# SCH_CyGarageM2.net
KiCad netlist of a schematic drawn in EasyEDA
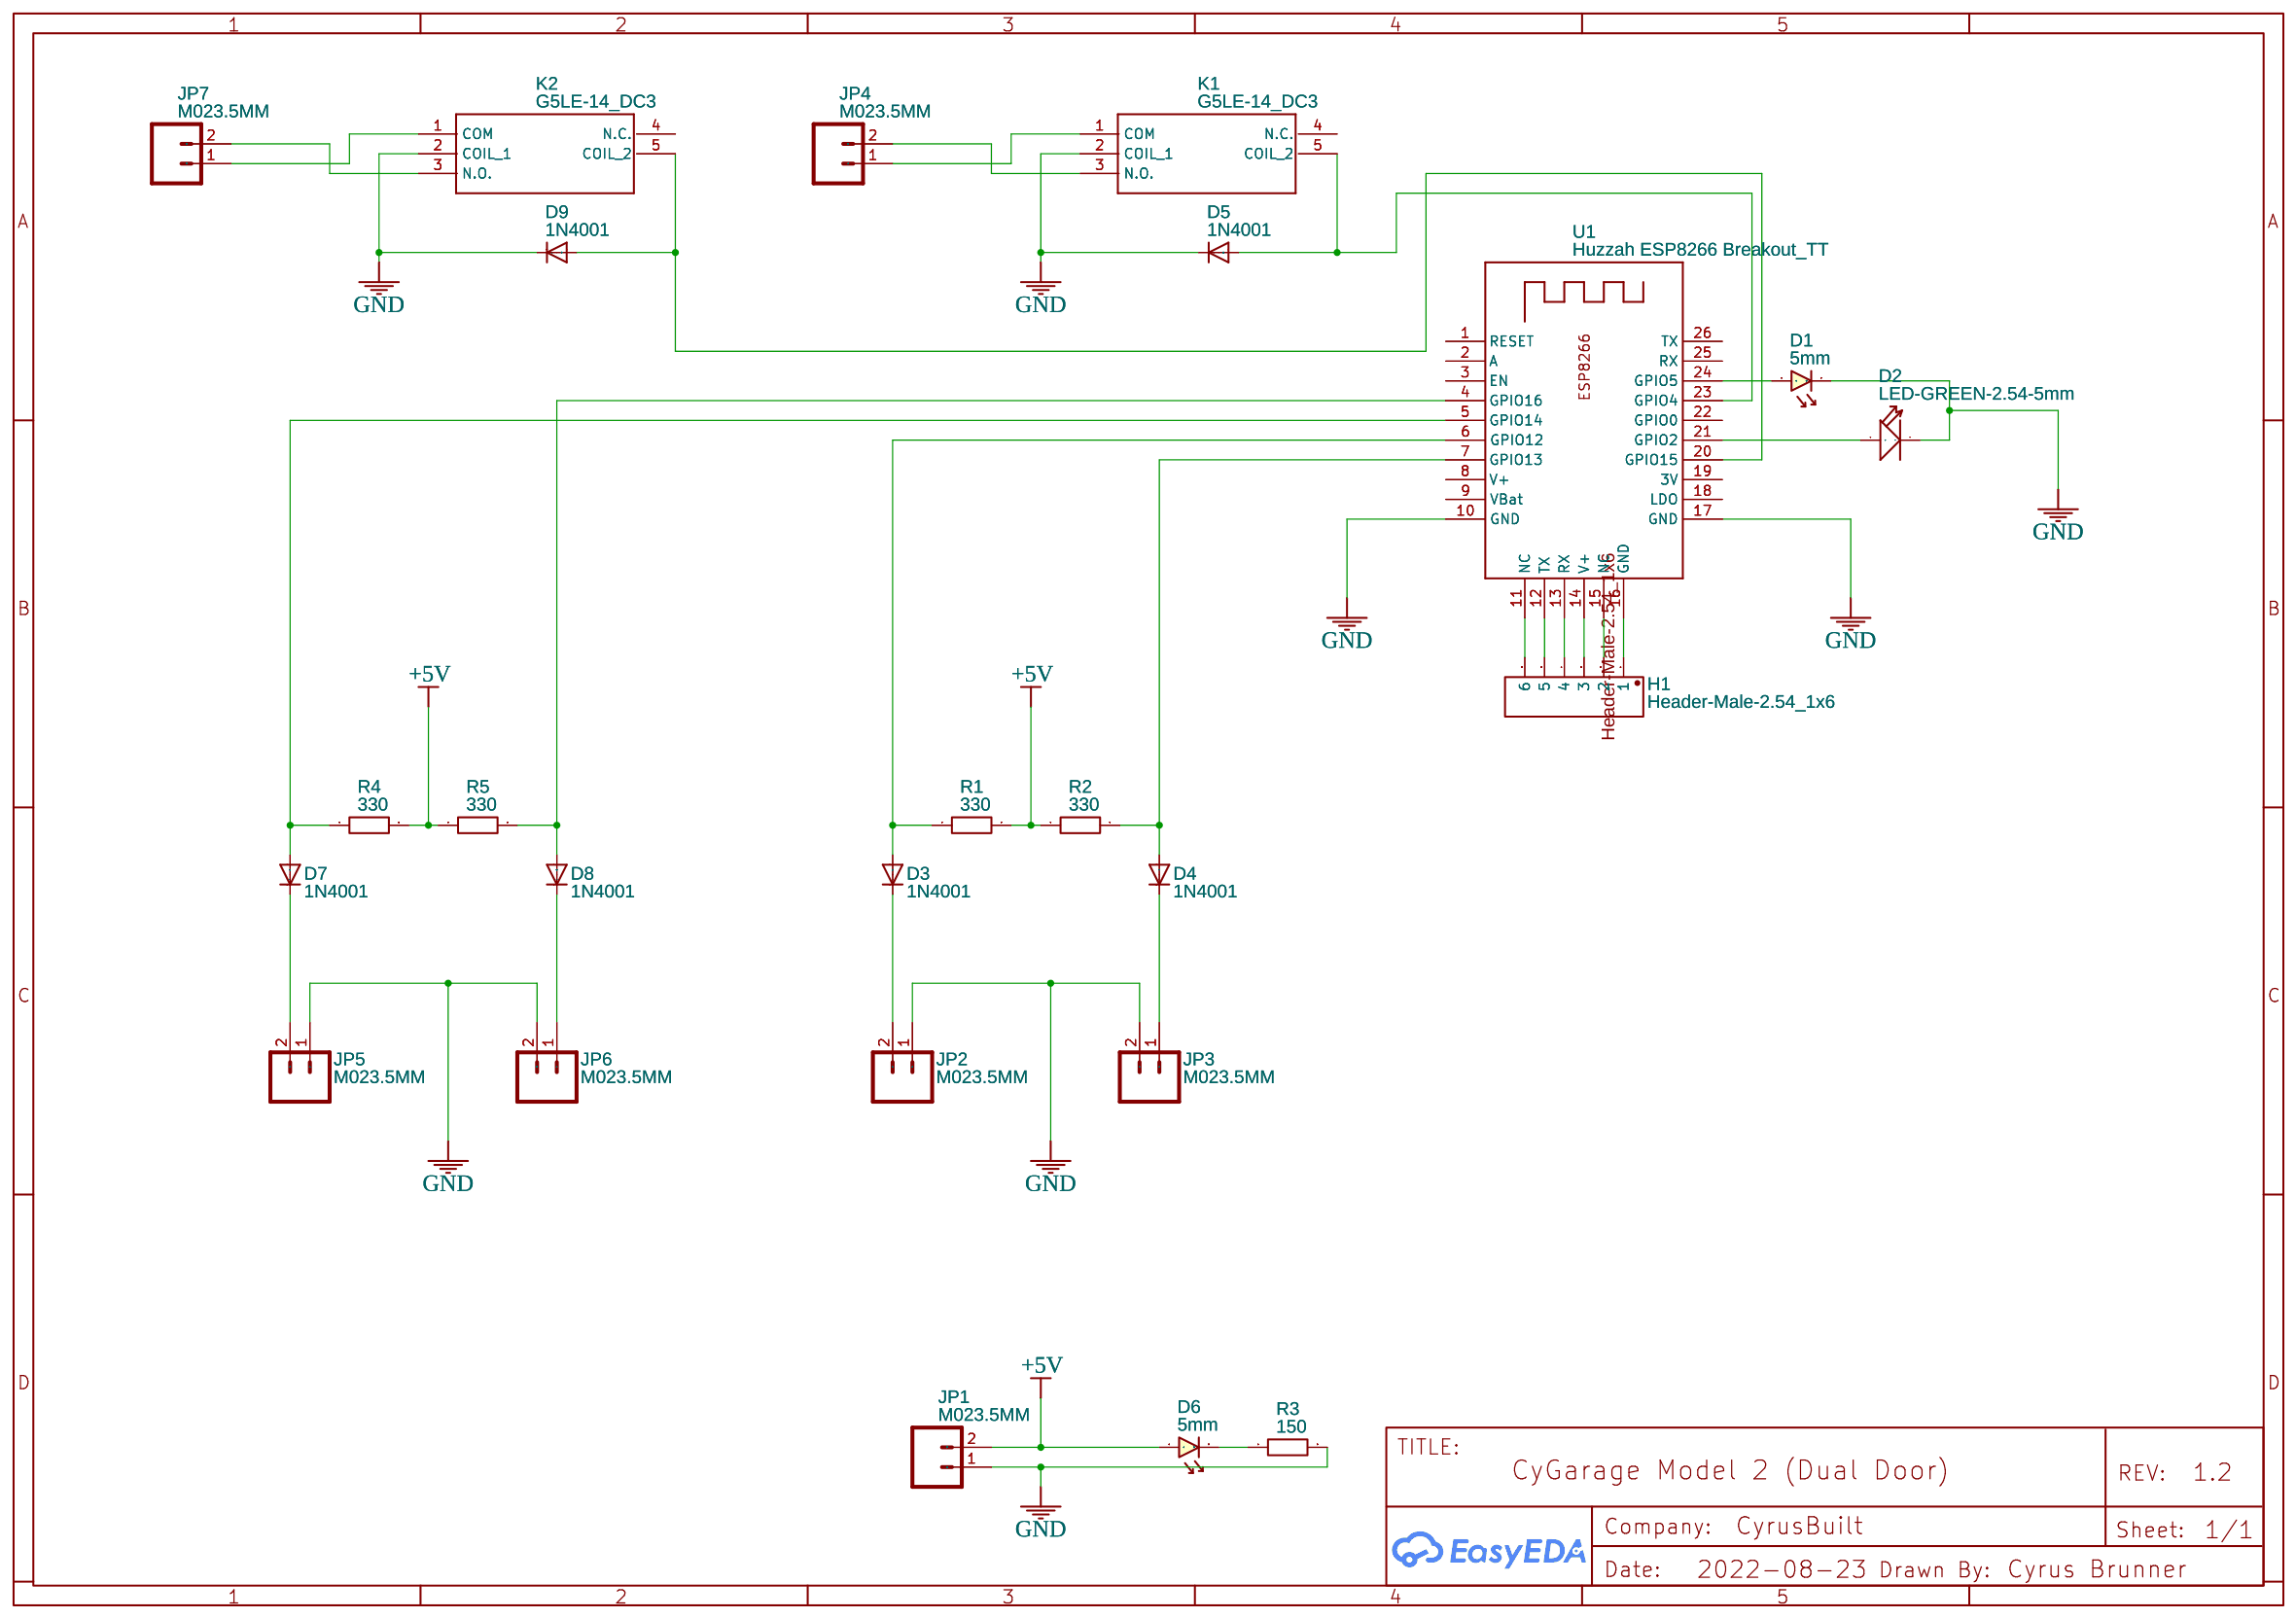
[diagram p0: schematic sheet]

(export (version "E")
  (design (tool "Eeschema 10.0.6"))
  (components
    (comp (ref "D1")
      (value "5mm")
      (fields (field (name "BOM_Manufacturer Part") "L-1503EC") (field (name "BOM_Supplier Part") "1003201"))
      (libsource (lib "") (part "L-1503EC"))
    )
    (comp (ref "D2")
      (value "LED-GREEN-2.54-5mm")
      (fields (field (name "BOM_Manufacturer Part") "503UOC"))
      (libsource (lib "") (part "LED-GREEN-2.54-5mm"))
    )
    (comp (ref "D3") (value "1N4001") (libsource (lib "") (part "1N4001")))
    (comp (ref "D4") (value "1N4001") (libsource (lib "") (part "1N4001")))
    (comp (ref "D5") (value "1N4001") (libsource (lib "") (part "1N4001_1")))
    (comp (ref "D6")
      (value "5mm")
      (fields (field (name "BOM_Manufacturer Part") "L-1503EC") (field (name "BOM_Supplier Part") "1003201"))
      (libsource (lib "") (part "L-1503EC"))
    )
    (comp (ref "D7") (value "1N4001") (libsource (lib "") (part "1N4001")))
    (comp (ref "D8") (value "1N4001") (libsource (lib "") (part "1N4001")))
    (comp (ref "D9") (value "1N4001") (libsource (lib "") (part "1N4001_1")))
    (comp (ref "H1") (value "Header-Male-2.54_1x6") (libsource (lib "") (part "Header-Male-2.54_1x6")))
    (comp (ref "JP1") (value "M023.5MM") (libsource (lib "") (part "M023.5MM_1")))
    (comp (ref "JP2") (value "M023.5MM") (libsource (lib "") (part "M023.5MM")))
    (comp (ref "JP3") (value "M023.5MM") (libsource (lib "") (part "M023.5MM")))
    (comp (ref "JP4") (value "M023.5MM") (libsource (lib "") (part "M023.5MM_1")))
    (comp (ref "JP5") (value "M023.5MM") (libsource (lib "") (part "M023.5MM")))
    (comp (ref "JP6") (value "M023.5MM") (libsource (lib "") (part "M023.5MM")))
    (comp (ref "JP7") (value "M023.5MM") (libsource (lib "") (part "M023.5MM_1")))
    (comp (ref "K1") (value "G5LE-14_DC3") (libsource (lib "") (part "G5LE-14_DC3")))
    (comp (ref "K2") (value "G5LE-14_DC3") (libsource (lib "") (part "G5LE-14_DC3")))
    (comp (ref "R1") (value "330") (libsource (lib "") (part "330")))
    (comp (ref "R2") (value "330") (libsource (lib "") (part "330")))
    (comp (ref "R3") (value "150") (libsource (lib "") (part "150")))
    (comp (ref "R4") (value "330") (libsource (lib "") (part "330")))
    (comp (ref "R5") (value "330") (libsource (lib "") (part "330")))
    (comp (ref "U1")
      (value "Huzzah ESP8266 Breakout_TT")
      (libsource (lib "") (part "Huzzah ESP8266 Breakout_TT"))
    )
  )
  (nets
    (net (code "1") (name "+5V") (class "Default")
      (node (ref "D6") (pin "1") (pinfunction "1_1") (pintype "unspecified"))
      (node (ref "JP1") (pin "2") (pinfunction "2_2") (pintype "unspecified"))
      (node (ref "R1") (pin "2") (pintype "unspecified"))
      (node (ref "R2") (pin "1") (pintype "unspecified"))
      (node (ref "R4") (pin "2") (pintype "unspecified"))
      (node (ref "R5") (pin "1") (pintype "unspecified"))
    )
    (net (code "2") (name "GND") (class "Default")
      (node (ref "D1") (pin "2") (pinfunction "2_2") (pintype "unspecified"))
      (node (ref "D2") (pin "-") (pinfunction "-_-") (pintype "unspecified"))
      (node (ref "D5") (pin "C") (pinfunction "C_C") (pintype "unspecified"))
      (node (ref "D9") (pin "C") (pinfunction "C_C") (pintype "unspecified"))
      (node (ref "JP1") (pin "1") (pinfunction "1_1") (pintype "unspecified"))
      (node (ref "JP2") (pin "1") (pinfunction "1_1") (pintype "unspecified"))
      (node (ref "JP3") (pin "2") (pinfunction "2_2") (pintype "unspecified"))
      (node (ref "JP5") (pin "1") (pinfunction "1_1") (pintype "unspecified"))
      (node (ref "JP6") (pin "2") (pinfunction "2_2") (pintype "unspecified"))
      (node (ref "K1") (pin "2") (pinfunction "COIL_1_2") (pintype "bidirectional"))
      (node (ref "K2") (pin "2") (pinfunction "COIL_1_2") (pintype "bidirectional"))
      (node (ref "R3") (pin "2") (pintype "unspecified"))
      (node (ref "U1") (pin "10") (pinfunction "GND_10") (pintype "unspecified"))
      (node (ref "U1") (pin "17") (pinfunction "GND_17") (pintype "unspecified"))
    )
    (net (code "3") (name "Net-(D3-PadC)") (class "Default")
      (node (ref "D3") (pin "C") (pinfunction "C_C") (pintype "unspecified"))
      (node (ref "JP2") (pin "2") (pinfunction "2_2") (pintype "unspecified"))
    )
    (net (code "4") (name "Net-(D4-PadC)") (class "Default")
      (node (ref "D4") (pin "C") (pinfunction "C_C") (pintype "unspecified"))
      (node (ref "JP3") (pin "1") (pinfunction "1_1") (pintype "unspecified"))
    )
    (net (code "5") (name "Net-(D6-Pad2)") (class "Default")
      (node (ref "D6") (pin "2") (pinfunction "2_2") (pintype "unspecified"))
      (node (ref "R3") (pin "1") (pintype "unspecified"))
    )
    (net (code "6") (name "Net-(D7-PadC)") (class "Default")
      (node (ref "D7") (pin "C") (pinfunction "C_C") (pintype "unspecified"))
      (node (ref "JP5") (pin "2") (pinfunction "2_2") (pintype "unspecified"))
    )
    (net (code "7") (name "Net-(D8-PadC)") (class "Default")
      (node (ref "D8") (pin "C") (pinfunction "C_C") (pintype "unspecified"))
      (node (ref "JP6") (pin "1") (pinfunction "1_1") (pintype "unspecified"))
    )
    (net (code "8") (name "Net-(H1-Pad1)") (class "Default")
      (node (ref "H1") (pin "1") (pinfunction "1_1") (pintype "unspecified"))
      (node (ref "U1") (pin "16") (pinfunction "GND_16") (pintype "unspecified"))
    )
    (net (code "9") (name "Net-(H1-Pad2)") (class "Default")
      (node (ref "H1") (pin "2") (pinfunction "2_2") (pintype "unspecified"))
      (node (ref "U1") (pin "15") (pinfunction "NC_15") (pintype "unspecified"))
    )
    (net (code "10") (name "Net-(H1-Pad3)") (class "Default")
      (node (ref "H1") (pin "3") (pinfunction "3_3") (pintype "unspecified"))
      (node (ref "U1") (pin "14") (pinfunction "V+_14") (pintype "unspecified"))
    )
    (net (code "11") (name "Net-(H1-Pad4)") (class "Default")
      (node (ref "H1") (pin "4") (pinfunction "4_4") (pintype "unspecified"))
      (node (ref "U1") (pin "13") (pinfunction "RX_13") (pintype "unspecified"))
    )
    (net (code "12") (name "Net-(H1-Pad5)") (class "Default")
      (node (ref "H1") (pin "5") (pinfunction "5_5") (pintype "unspecified"))
      (node (ref "U1") (pin "12") (pinfunction "TX_12") (pintype "unspecified"))
    )
    (net (code "13") (name "Net-(H1-Pad6)") (class "Default")
      (node (ref "H1") (pin "6") (pinfunction "6_6") (pintype "unspecified"))
      (node (ref "U1") (pin "11") (pinfunction "NC_11") (pintype "unspecified"))
    )
    (net (code "14") (name "Net-(K1-COIL_2)") (class "Default")
      (node (ref "D5") (pin "A") (pinfunction "A_A") (pintype "unspecified"))
      (node (ref "K1") (pin "5") (pinfunction "COIL_2_5") (pintype "bidirectional"))
      (node (ref "U1") (pin "23") (pinfunction "GPIO4_23") (pintype "bidirectional"))
    )
    (net (code "15") (name "Net-(K1-COM)") (class "Default")
      (node (ref "JP4") (pin "1") (pinfunction "1_1") (pintype "unspecified"))
      (node (ref "K1") (pin "1") (pinfunction "COM_1") (pintype "bidirectional"))
    )
    (net (code "16") (name "Net-(K1-N.O.)") (class "Default")
      (node (ref "JP4") (pin "2") (pinfunction "2_2") (pintype "unspecified"))
      (node (ref "K1") (pin "3") (pinfunction "N.O._3") (pintype "bidirectional"))
    )
    (net (code "17") (name "Net-(K2-COIL_2)") (class "Default")
      (node (ref "D9") (pin "A") (pinfunction "A_A") (pintype "unspecified"))
      (node (ref "K2") (pin "5") (pinfunction "COIL_2_5") (pintype "bidirectional"))
      (node (ref "U1") (pin "20") (pinfunction "GPIO15_20") (pintype "bidirectional"))
    )
    (net (code "18") (name "Net-(K2-COM)") (class "Default")
      (node (ref "JP7") (pin "1") (pinfunction "1_1") (pintype "unspecified"))
      (node (ref "K2") (pin "1") (pinfunction "COM_1") (pintype "bidirectional"))
    )
    (net (code "19") (name "Net-(K2-N.O.)") (class "Default")
      (node (ref "JP7") (pin "2") (pinfunction "2_2") (pintype "unspecified"))
      (node (ref "K2") (pin "3") (pinfunction "N.O._3") (pintype "bidirectional"))
    )
    (net (code "20") (name "Net-(U1-GPIO2)") (class "Default")
      (node (ref "D2") (pin "+") (pinfunction "+_+") (pintype "unspecified"))
      (node (ref "U1") (pin "21") (pinfunction "GPIO2_21") (pintype "bidirectional"))
    )
    (net (code "21") (name "Net-(U1-GPIO5)") (class "Default")
      (node (ref "D1") (pin "1") (pinfunction "1_1") (pintype "unspecified"))
      (node (ref "U1") (pin "24") (pinfunction "GPIO5_24") (pintype "bidirectional"))
    )
    (net (code "22") (name "Net-(U1-GPIO12)") (class "Default")
      (node (ref "D3") (pin "A") (pinfunction "A_A") (pintype "unspecified"))
      (node (ref "R1") (pin "1") (pintype "unspecified"))
      (node (ref "U1") (pin "6") (pinfunction "GPIO12_6") (pintype "unspecified"))
    )
    (net (code "23") (name "Net-(U1-GPIO13)") (class "Default")
      (node (ref "D4") (pin "A") (pinfunction "A_A") (pintype "unspecified"))
      (node (ref "R2") (pin "2") (pintype "unspecified"))
      (node (ref "U1") (pin "7") (pinfunction "GPIO13_7") (pintype "bidirectional"))
    )
    (net (code "24") (name "Net-(U1-GPIO14)") (class "Default")
      (node (ref "D7") (pin "A") (pinfunction "A_A") (pintype "unspecified"))
      (node (ref "R4") (pin "1") (pintype "unspecified"))
      (node (ref "U1") (pin "5") (pinfunction "GPIO14_5") (pintype "bidirectional"))
    )
    (net (code "25") (name "Net-(U1-GPIO16)") (class "Default")
      (node (ref "D8") (pin "A") (pinfunction "A_A") (pintype "unspecified"))
      (node (ref "R5") (pin "2") (pintype "unspecified"))
      (node (ref "U1") (pin "4") (pinfunction "GPIO16_4") (pintype "bidirectional"))
    )
    (net (code "26") (name "unconnected-(K1-N.C.-Pad4)") (class "Default")
      (node (ref "K1") (pin "4") (pinfunction "N.C._4") (pintype "bidirectional"))
    )
    (net (code "27") (name "unconnected-(K2-N.C.-Pad4)") (class "Default")
      (node (ref "K2") (pin "4") (pinfunction "N.C._4") (pintype "bidirectional"))
    )
    (net (code "28") (name "unconnected-(U1-3V-Pad19)") (class "Default")
      (node (ref "U1") (pin "19") (pinfunction "3V_19") (pintype "unspecified"))
    )
    (net (code "29") (name "unconnected-(U1-A-Pad2)") (class "Default")
      (node (ref "U1") (pin "2") (pinfunction "A_2") (pintype "bidirectional"))
    )
    (net (code "30") (name "unconnected-(U1-EN-Pad3)") (class "Default")
      (node (ref "U1") (pin "3") (pinfunction "EN_3") (pintype "bidirectional"))
    )
    (net (code "31") (name "unconnected-(U1-GPIO0-Pad22)") (class "Default")
      (node (ref "U1") (pin "22") (pinfunction "GPIO0_22") (pintype "bidirectional"))
    )
    (net (code "32") (name "unconnected-(U1-LDO-Pad18)") (class "Default")
      (node (ref "U1") (pin "18") (pinfunction "LDO_18") (pintype "unspecified"))
    )
    (net (code "33") (name "unconnected-(U1-RESET-Pad1)") (class "Default")
      (node (ref "U1") (pin "1") (pinfunction "RESET_1") (pintype "bidirectional"))
    )
    (net (code "34") (name "unconnected-(U1-RX-Pad25)") (class "Default")
      (node (ref "U1") (pin "25") (pinfunction "RX_25") (pintype "bidirectional"))
    )
    (net (code "35") (name "unconnected-(U1-TX-Pad26)") (class "Default")
      (node (ref "U1") (pin "26") (pinfunction "TX_26") (pintype "bidirectional"))
    )
    (net (code "36") (name "unconnected-(U1-V+-Pad8)") (class "Default")
      (node (ref "U1") (pin "8") (pinfunction "V+_8") (pintype "bidirectional"))
    )
    (net (code "37") (name "unconnected-(U1-VBat-Pad9)") (class "Default")
      (node (ref "U1") (pin "9") (pinfunction "VBat_9") (pintype "unspecified"))
    )
  )
)
